# SCH_circular-led_2022-01-28.net
KiCad netlist of a schematic drawn in EasyEDA
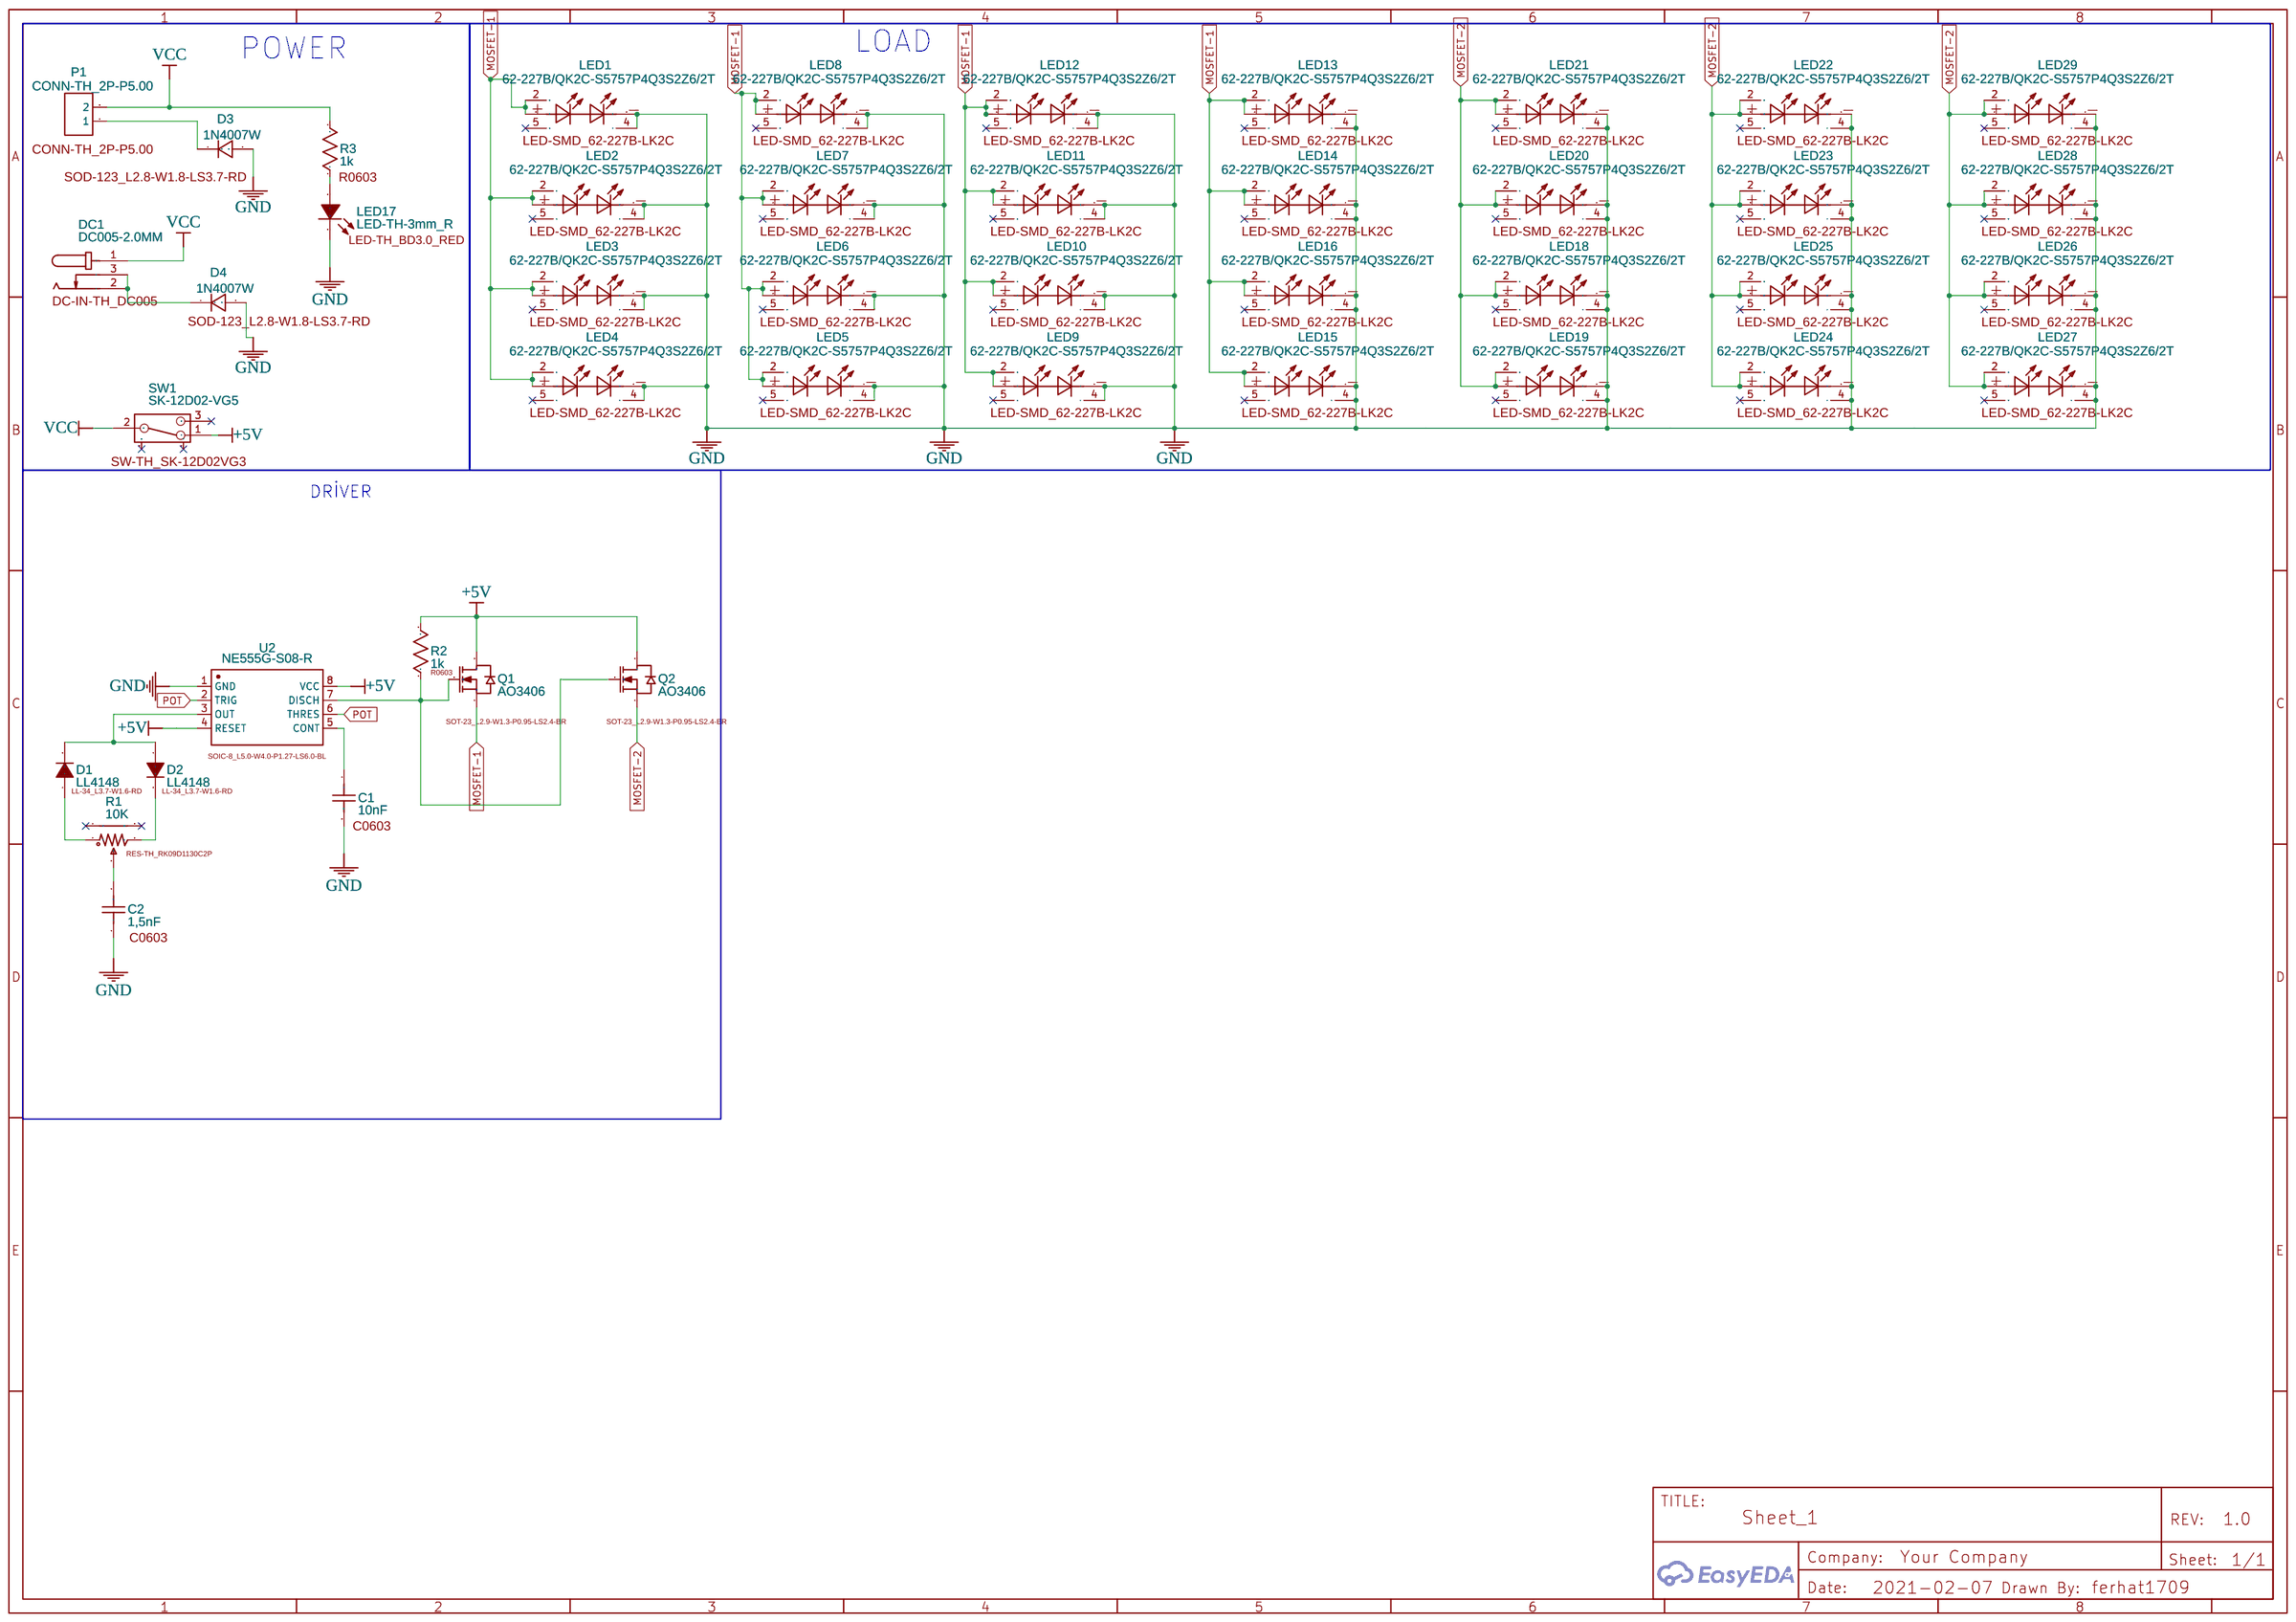
[diagram p0: schematic sheet]

(export (version "E")
  (design (tool "Eeschema 10.0.6"))
  (components
    (comp (ref "C1") (value "10nF") (libsource (lib "") (part "C_0603_US")))
    (comp (ref "C2") (value "1,5nF") (libsource (lib "") (part "C_0603_US_1")))
    (comp (ref "D1")
      (value "LL4148")
      (fields (field (name "BOM_Supplier Part") "C9808"))
      (libsource (lib "") (part "LL4148"))
    )
    (comp (ref "D2")
      (value "LL4148")
      (fields (field (name "BOM_Supplier Part") "C9808"))
      (libsource (lib "") (part "LL4148_1"))
    )
    (comp (ref "D3")
      (value "1N4007W")
      (fields (field (name "BOM_Supplier Part") "C328592"))
      (libsource (lib "") (part "1N4007W"))
    )
    (comp (ref "D4")
      (value "1N4007W")
      (fields (field (name "BOM_Supplier Part") "C328592"))
      (libsource (lib "") (part "1N4007W_1"))
    )
    (comp (ref "DC1")
      (value "DC005-2.0MM")
      (fields (field (name "BOM_Supplier Part") "C111567"))
      (libsource (lib "") (part "DC005-2.0MM"))
    )
    (comp (ref "LED1")
      (value "62-227B/QK2C-S5757P4Q3S2Z6/2T")
      (fields (field (name "BOM_Supplier Part") "C282160"))
      (libsource (lib "") (part "62-227B/QK2C-S5757P4Q3S2Z6/2T"))
    )
    (comp (ref "LED2")
      (value "62-227B/QK2C-S5757P4Q3S2Z6/2T")
      (fields (field (name "BOM_Supplier Part") "C282160"))
      (libsource (lib "") (part "62-227B/QK2C-S5757P4Q3S2Z6/2T"))
    )
    (comp (ref "LED3")
      (value "62-227B/QK2C-S5757P4Q3S2Z6/2T")
      (fields (field (name "BOM_Supplier Part") "C282160"))
      (libsource (lib "") (part "62-227B/QK2C-S5757P4Q3S2Z6/2T"))
    )
    (comp (ref "LED4")
      (value "62-227B/QK2C-S5757P4Q3S2Z6/2T")
      (fields (field (name "BOM_Supplier Part") "C282160"))
      (libsource (lib "") (part "62-227B/QK2C-S5757P4Q3S2Z6/2T"))
    )
    (comp (ref "LED5")
      (value "62-227B/QK2C-S5757P4Q3S2Z6/2T")
      (fields (field (name "BOM_Supplier Part") "C282160"))
      (libsource (lib "") (part "62-227B/QK2C-S5757P4Q3S2Z6/2T"))
    )
    (comp (ref "LED6")
      (value "62-227B/QK2C-S5757P4Q3S2Z6/2T")
      (fields (field (name "BOM_Supplier Part") "C282160"))
      (libsource (lib "") (part "62-227B/QK2C-S5757P4Q3S2Z6/2T"))
    )
    (comp (ref "LED7")
      (value "62-227B/QK2C-S5757P4Q3S2Z6/2T")
      (fields (field (name "BOM_Supplier Part") "C282160"))
      (libsource (lib "") (part "62-227B/QK2C-S5757P4Q3S2Z6/2T"))
    )
    (comp (ref "LED8")
      (value "62-227B/QK2C-S5757P4Q3S2Z6/2T")
      (fields (field (name "BOM_Supplier Part") "C282160"))
      (libsource (lib "") (part "62-227B/QK2C-S5757P4Q3S2Z6/2T"))
    )
    (comp (ref "LED9")
      (value "62-227B/QK2C-S5757P4Q3S2Z6/2T")
      (fields (field (name "BOM_Supplier Part") "C282160"))
      (libsource (lib "") (part "62-227B/QK2C-S5757P4Q3S2Z6/2T"))
    )
    (comp (ref "LED10")
      (value "62-227B/QK2C-S5757P4Q3S2Z6/2T")
      (fields (field (name "BOM_Supplier Part") "C282160"))
      (libsource (lib "") (part "62-227B/QK2C-S5757P4Q3S2Z6/2T"))
    )
    (comp (ref "LED11")
      (value "62-227B/QK2C-S5757P4Q3S2Z6/2T")
      (fields (field (name "BOM_Supplier Part") "C282160"))
      (libsource (lib "") (part "62-227B/QK2C-S5757P4Q3S2Z6/2T"))
    )
    (comp (ref "LED12")
      (value "62-227B/QK2C-S5757P4Q3S2Z6/2T")
      (fields (field (name "BOM_Supplier Part") "C282160"))
      (libsource (lib "") (part "62-227B/QK2C-S5757P4Q3S2Z6/2T"))
    )
    (comp (ref "LED13")
      (value "62-227B/QK2C-S5757P4Q3S2Z6/2T")
      (fields (field (name "BOM_Supplier Part") "C282160"))
      (libsource (lib "") (part "62-227B/QK2C-S5757P4Q3S2Z6/2T"))
    )
    (comp (ref "LED14")
      (value "62-227B/QK2C-S5757P4Q3S2Z6/2T")
      (fields (field (name "BOM_Supplier Part") "C282160"))
      (libsource (lib "") (part "62-227B/QK2C-S5757P4Q3S2Z6/2T"))
    )
    (comp (ref "LED15")
      (value "62-227B/QK2C-S5757P4Q3S2Z6/2T")
      (fields (field (name "BOM_Supplier Part") "C282160"))
      (libsource (lib "") (part "62-227B/QK2C-S5757P4Q3S2Z6/2T"))
    )
    (comp (ref "LED16")
      (value "62-227B/QK2C-S5757P4Q3S2Z6/2T")
      (fields (field (name "BOM_Supplier Part") "C282160"))
      (libsource (lib "") (part "62-227B/QK2C-S5757P4Q3S2Z6/2T"))
    )
    (comp (ref "LED17")
      (value "LED-TH-3mm_R")
      (fields
        (field (name "BOM_Manufacturer Part") "204-10SDRD/S530-A3-L")
        (field (name "BOM_Supplier Part") "C84774")
      )
      (libsource (lib "") (part "LED-TH-3mm_R"))
    )
    (comp (ref "LED18")
      (value "62-227B/QK2C-S5757P4Q3S2Z6/2T")
      (fields (field (name "BOM_Supplier Part") "C282160"))
      (libsource (lib "") (part "62-227B/QK2C-S5757P4Q3S2Z6/2T"))
    )
    (comp (ref "LED19")
      (value "62-227B/QK2C-S5757P4Q3S2Z6/2T")
      (fields (field (name "BOM_Supplier Part") "C282160"))
      (libsource (lib "") (part "62-227B/QK2C-S5757P4Q3S2Z6/2T"))
    )
    (comp (ref "LED20")
      (value "62-227B/QK2C-S5757P4Q3S2Z6/2T")
      (fields (field (name "BOM_Supplier Part") "C282160"))
      (libsource (lib "") (part "62-227B/QK2C-S5757P4Q3S2Z6/2T"))
    )
    (comp (ref "LED21")
      (value "62-227B/QK2C-S5757P4Q3S2Z6/2T")
      (fields (field (name "BOM_Supplier Part") "C282160"))
      (libsource (lib "") (part "62-227B/QK2C-S5757P4Q3S2Z6/2T"))
    )
    (comp (ref "LED22")
      (value "62-227B/QK2C-S5757P4Q3S2Z6/2T")
      (fields (field (name "BOM_Supplier Part") "C282160"))
      (libsource (lib "") (part "62-227B/QK2C-S5757P4Q3S2Z6/2T"))
    )
    (comp (ref "LED23")
      (value "62-227B/QK2C-S5757P4Q3S2Z6/2T")
      (fields (field (name "BOM_Supplier Part") "C282160"))
      (libsource (lib "") (part "62-227B/QK2C-S5757P4Q3S2Z6/2T"))
    )
    (comp (ref "LED24")
      (value "62-227B/QK2C-S5757P4Q3S2Z6/2T")
      (fields (field (name "BOM_Supplier Part") "C282160"))
      (libsource (lib "") (part "62-227B/QK2C-S5757P4Q3S2Z6/2T"))
    )
    (comp (ref "LED25")
      (value "62-227B/QK2C-S5757P4Q3S2Z6/2T")
      (fields (field (name "BOM_Supplier Part") "C282160"))
      (libsource (lib "") (part "62-227B/QK2C-S5757P4Q3S2Z6/2T"))
    )
    (comp (ref "LED26")
      (value "62-227B/QK2C-S5757P4Q3S2Z6/2T")
      (fields (field (name "BOM_Supplier Part") "C282160"))
      (libsource (lib "") (part "62-227B/QK2C-S5757P4Q3S2Z6/2T"))
    )
    (comp (ref "LED27")
      (value "62-227B/QK2C-S5757P4Q3S2Z6/2T")
      (fields (field (name "BOM_Supplier Part") "C282160"))
      (libsource (lib "") (part "62-227B/QK2C-S5757P4Q3S2Z6/2T"))
    )
    (comp (ref "LED28")
      (value "62-227B/QK2C-S5757P4Q3S2Z6/2T")
      (fields (field (name "BOM_Supplier Part") "C282160"))
      (libsource (lib "") (part "62-227B/QK2C-S5757P4Q3S2Z6/2T"))
    )
    (comp (ref "LED29")
      (value "62-227B/QK2C-S5757P4Q3S2Z6/2T")
      (fields (field (name "BOM_Supplier Part") "C282160"))
      (libsource (lib "") (part "62-227B/QK2C-S5757P4Q3S2Z6/2T"))
    )
    (comp (ref "P1") (value "CONN-TH_2P-P5.00") (libsource (lib "") (part "CONN-TH_2P-P5.00")))
    (comp (ref "Q1")
      (value "AO3406")
      (fields (field (name "BOM_Supplier Part") "C88051"))
      (libsource (lib "") (part "AO3406"))
    )
    (comp (ref "Q2")
      (value "AO3406")
      (fields (field (name "BOM_Supplier Part") "C88051"))
      (libsource (lib "") (part "AO3406"))
    )
    (comp (ref "R1")
      (value "10K")
      (fields
        (field (name "BOM_Manufacturer Part") "RK09D1130C2P")
        (field (name "BOM_Supplier Part") "C361173")
      )
      (libsource (lib "") (part "RK09D1130C2P"))
    )
    (comp (ref "R2") (value "1k") (libsource (lib "") (part "R_0603_US")))
    (comp (ref "R3") (value "1k") (libsource (lib "") (part "R_0603_US_1")))
    (comp (ref "SW1")
      (value "SK-12D02-VG5")
      (fields (field (name "BOM_Supplier Part") "C136722"))
      (libsource (lib "") (part "SK-12D02-VG5"))
    )
    (comp (ref "U2")
      (value "NE555G-S08-R")
      (fields (field (name "BOM_Supplier Part") "C75529"))
      (libsource (lib "") (part "NE555G-S08-R"))
    )
  )
  (nets
    (net (code "1") (name "+5V") (class "Default")
      (node (ref "Q1") (pin "3") (pinfunction "D_3") (pintype "unspecified"))
      (node (ref "Q2") (pin "3") (pinfunction "D_3") (pintype "unspecified"))
      (node (ref "R2") (pin "2") (pinfunction "2_2") (pintype "unspecified"))
      (node (ref "SW1") (pin "1") (pinfunction "1_1") (pintype "unspecified"))
      (node (ref "U2") (pin "4") (pinfunction "RESET_4") (pintype "unspecified"))
      (node (ref "U2") (pin "8") (pinfunction "VCC_8") (pintype "unspecified"))
    )
    (net (code "2") (name "GND") (class "Default")
      (node (ref "C1") (pin "2") (pinfunction "2_2") (pintype "unspecified"))
      (node (ref "C2") (pin "1") (pinfunction "1_1") (pintype "unspecified"))
      (node (ref "D3") (pin "2") (pinfunction "2_2") (pintype "unspecified"))
      (node (ref "D4") (pin "2") (pinfunction "2_2") (pintype "unspecified"))
      (node (ref "LED1") (pin "1") (pinfunction "1_1") (pintype "unspecified"))
      (node (ref "LED1") (pin "4") (pinfunction "4_4") (pintype "unspecified"))
      (node (ref "LED10") (pin "1") (pinfunction "1_1") (pintype "unspecified"))
      (node (ref "LED10") (pin "4") (pinfunction "4_4") (pintype "unspecified"))
      (node (ref "LED11") (pin "1") (pinfunction "1_1") (pintype "unspecified"))
      (node (ref "LED11") (pin "4") (pinfunction "4_4") (pintype "unspecified"))
      (node (ref "LED12") (pin "1") (pinfunction "1_1") (pintype "unspecified"))
      (node (ref "LED12") (pin "4") (pinfunction "4_4") (pintype "unspecified"))
      (node (ref "LED13") (pin "1") (pinfunction "1_1") (pintype "unspecified"))
      (node (ref "LED13") (pin "4") (pinfunction "4_4") (pintype "unspecified"))
      (node (ref "LED14") (pin "1") (pinfunction "1_1") (pintype "unspecified"))
      (node (ref "LED14") (pin "4") (pinfunction "4_4") (pintype "unspecified"))
      (node (ref "LED15") (pin "1") (pinfunction "1_1") (pintype "unspecified"))
      (node (ref "LED15") (pin "4") (pinfunction "4_4") (pintype "unspecified"))
      (node (ref "LED16") (pin "1") (pinfunction "1_1") (pintype "unspecified"))
      (node (ref "LED16") (pin "4") (pinfunction "4_4") (pintype "unspecified"))
      (node (ref "LED17") (pin "2") (pinfunction "2_2") (pintype "unspecified"))
      (node (ref "LED18") (pin "1") (pinfunction "1_1") (pintype "unspecified"))
      (node (ref "LED18") (pin "4") (pinfunction "4_4") (pintype "unspecified"))
      (node (ref "LED19") (pin "1") (pinfunction "1_1") (pintype "unspecified"))
      (node (ref "LED19") (pin "4") (pinfunction "4_4") (pintype "unspecified"))
      (node (ref "LED2") (pin "1") (pinfunction "1_1") (pintype "unspecified"))
      (node (ref "LED2") (pin "4") (pinfunction "4_4") (pintype "unspecified"))
      (node (ref "LED20") (pin "1") (pinfunction "1_1") (pintype "unspecified"))
      (node (ref "LED20") (pin "4") (pinfunction "4_4") (pintype "unspecified"))
      (node (ref "LED21") (pin "1") (pinfunction "1_1") (pintype "unspecified"))
      (node (ref "LED21") (pin "4") (pinfunction "4_4") (pintype "unspecified"))
      (node (ref "LED22") (pin "1") (pinfunction "1_1") (pintype "unspecified"))
      (node (ref "LED22") (pin "4") (pinfunction "4_4") (pintype "unspecified"))
      (node (ref "LED23") (pin "1") (pinfunction "1_1") (pintype "unspecified"))
      (node (ref "LED23") (pin "4") (pinfunction "4_4") (pintype "unspecified"))
      (node (ref "LED24") (pin "1") (pinfunction "1_1") (pintype "unspecified"))
      (node (ref "LED24") (pin "4") (pinfunction "4_4") (pintype "unspecified"))
      (node (ref "LED25") (pin "1") (pinfunction "1_1") (pintype "unspecified"))
      (node (ref "LED25") (pin "4") (pinfunction "4_4") (pintype "unspecified"))
      (node (ref "LED26") (pin "1") (pinfunction "1_1") (pintype "unspecified"))
      (node (ref "LED26") (pin "4") (pinfunction "4_4") (pintype "unspecified"))
      (node (ref "LED27") (pin "1") (pinfunction "1_1") (pintype "unspecified"))
      (node (ref "LED27") (pin "4") (pinfunction "4_4") (pintype "unspecified"))
      (node (ref "LED28") (pin "1") (pinfunction "1_1") (pintype "unspecified"))
      (node (ref "LED28") (pin "4") (pinfunction "4_4") (pintype "unspecified"))
      (node (ref "LED29") (pin "1") (pinfunction "1_1") (pintype "unspecified"))
      (node (ref "LED29") (pin "4") (pinfunction "4_4") (pintype "unspecified"))
      (node (ref "LED3") (pin "1") (pinfunction "1_1") (pintype "unspecified"))
      (node (ref "LED3") (pin "4") (pinfunction "4_4") (pintype "unspecified"))
      (node (ref "LED4") (pin "1") (pinfunction "1_1") (pintype "unspecified"))
      (node (ref "LED4") (pin "4") (pinfunction "4_4") (pintype "unspecified"))
      (node (ref "LED5") (pin "1") (pinfunction "1_1") (pintype "unspecified"))
      (node (ref "LED5") (pin "4") (pinfunction "4_4") (pintype "unspecified"))
      (node (ref "LED6") (pin "1") (pinfunction "1_1") (pintype "unspecified"))
      (node (ref "LED6") (pin "4") (pinfunction "4_4") (pintype "unspecified"))
      (node (ref "LED7") (pin "1") (pinfunction "1_1") (pintype "unspecified"))
      (node (ref "LED7") (pin "4") (pinfunction "4_4") (pintype "unspecified"))
      (node (ref "LED8") (pin "1") (pinfunction "1_1") (pintype "unspecified"))
      (node (ref "LED8") (pin "4") (pinfunction "4_4") (pintype "unspecified"))
      (node (ref "LED9") (pin "1") (pinfunction "1_1") (pintype "unspecified"))
      (node (ref "LED9") (pin "4") (pinfunction "4_4") (pintype "unspecified"))
      (node (ref "U2") (pin "1") (pinfunction "GND_1") (pintype "unspecified"))
    )
    (net (code "3") (name "MOSFET-1") (class "Default")
      (node (ref "LED1") (pin "2") (pinfunction "2_2") (pintype "unspecified"))
      (node (ref "LED1") (pin "3") (pinfunction "3_3") (pintype "unspecified"))
      (node (ref "LED10") (pin "2") (pinfunction "2_2") (pintype "unspecified"))
      (node (ref "LED10") (pin "3") (pinfunction "3_3") (pintype "unspecified"))
      (node (ref "LED11") (pin "2") (pinfunction "2_2") (pintype "unspecified"))
      (node (ref "LED11") (pin "3") (pinfunction "3_3") (pintype "unspecified"))
      (node (ref "LED12") (pin "2") (pinfunction "2_2") (pintype "unspecified"))
      (node (ref "LED12") (pin "3") (pinfunction "3_3") (pintype "unspecified"))
      (node (ref "LED13") (pin "2") (pinfunction "2_2") (pintype "unspecified"))
      (node (ref "LED13") (pin "3") (pinfunction "3_3") (pintype "unspecified"))
      (node (ref "LED14") (pin "2") (pinfunction "2_2") (pintype "unspecified"))
      (node (ref "LED14") (pin "3") (pinfunction "3_3") (pintype "unspecified"))
      (node (ref "LED15") (pin "2") (pinfunction "2_2") (pintype "unspecified"))
      (node (ref "LED15") (pin "3") (pinfunction "3_3") (pintype "unspecified"))
      (node (ref "LED16") (pin "2") (pinfunction "2_2") (pintype "unspecified"))
      (node (ref "LED16") (pin "3") (pinfunction "3_3") (pintype "unspecified"))
      (node (ref "LED2") (pin "2") (pinfunction "2_2") (pintype "unspecified"))
      (node (ref "LED2") (pin "3") (pinfunction "3_3") (pintype "unspecified"))
      (node (ref "LED3") (pin "2") (pinfunction "2_2") (pintype "unspecified"))
      (node (ref "LED3") (pin "3") (pinfunction "3_3") (pintype "unspecified"))
      (node (ref "LED4") (pin "2") (pinfunction "2_2") (pintype "unspecified"))
      (node (ref "LED4") (pin "3") (pinfunction "3_3") (pintype "unspecified"))
      (node (ref "LED5") (pin "2") (pinfunction "2_2") (pintype "unspecified"))
      (node (ref "LED5") (pin "3") (pinfunction "3_3") (pintype "unspecified"))
      (node (ref "LED6") (pin "2") (pinfunction "2_2") (pintype "unspecified"))
      (node (ref "LED6") (pin "3") (pinfunction "3_3") (pintype "unspecified"))
      (node (ref "LED7") (pin "2") (pinfunction "2_2") (pintype "unspecified"))
      (node (ref "LED7") (pin "3") (pinfunction "3_3") (pintype "unspecified"))
      (node (ref "LED8") (pin "2") (pinfunction "2_2") (pintype "unspecified"))
      (node (ref "LED8") (pin "3") (pinfunction "3_3") (pintype "unspecified"))
      (node (ref "LED9") (pin "2") (pinfunction "2_2") (pintype "unspecified"))
      (node (ref "LED9") (pin "3") (pinfunction "3_3") (pintype "unspecified"))
      (node (ref "Q1") (pin "2") (pinfunction "S_2") (pintype "unspecified"))
    )
    (net (code "4") (name "MOSFET-2") (class "Default")
      (node (ref "LED18") (pin "2") (pinfunction "2_2") (pintype "unspecified"))
      (node (ref "LED18") (pin "3") (pinfunction "3_3") (pintype "unspecified"))
      (node (ref "LED19") (pin "2") (pinfunction "2_2") (pintype "unspecified"))
      (node (ref "LED19") (pin "3") (pinfunction "3_3") (pintype "unspecified"))
      (node (ref "LED20") (pin "2") (pinfunction "2_2") (pintype "unspecified"))
      (node (ref "LED20") (pin "3") (pinfunction "3_3") (pintype "unspecified"))
      (node (ref "LED21") (pin "2") (pinfunction "2_2") (pintype "unspecified"))
      (node (ref "LED21") (pin "3") (pinfunction "3_3") (pintype "unspecified"))
      (node (ref "LED22") (pin "2") (pinfunction "2_2") (pintype "unspecified"))
      (node (ref "LED22") (pin "3") (pinfunction "3_3") (pintype "unspecified"))
      (node (ref "LED23") (pin "2") (pinfunction "2_2") (pintype "unspecified"))
      (node (ref "LED23") (pin "3") (pinfunction "3_3") (pintype "unspecified"))
      (node (ref "LED24") (pin "2") (pinfunction "2_2") (pintype "unspecified"))
      (node (ref "LED24") (pin "3") (pinfunction "3_3") (pintype "unspecified"))
      (node (ref "LED25") (pin "2") (pinfunction "2_2") (pintype "unspecified"))
      (node (ref "LED25") (pin "3") (pinfunction "3_3") (pintype "unspecified"))
      (node (ref "LED26") (pin "2") (pinfunction "2_2") (pintype "unspecified"))
      (node (ref "LED26") (pin "3") (pinfunction "3_3") (pintype "unspecified"))
      (node (ref "LED27") (pin "2") (pinfunction "2_2") (pintype "unspecified"))
      (node (ref "LED27") (pin "3") (pinfunction "3_3") (pintype "unspecified"))
      (node (ref "LED28") (pin "2") (pinfunction "2_2") (pintype "unspecified"))
      (node (ref "LED28") (pin "3") (pinfunction "3_3") (pintype "unspecified"))
      (node (ref "LED29") (pin "2") (pinfunction "2_2") (pintype "unspecified"))
      (node (ref "LED29") (pin "3") (pinfunction "3_3") (pintype "unspecified"))
      (node (ref "Q2") (pin "2") (pinfunction "S_2") (pintype "unspecified"))
    )
    (net (code "5") (name "Net-(C2-Pad2)") (class "Default")
      (node (ref "C2") (pin "2") (pinfunction "2_2") (pintype "unspecified"))
      (node (ref "R1") (pin "2") (pinfunction "2_2") (pintype "unspecified"))
    )
    (net (code "6") (name "Net-(D1-A)") (class "Default")
      (node (ref "D1") (pin "1") (pinfunction "A_1") (pintype "unspecified"))
      (node (ref "R1") (pin "1") (pinfunction "1_1") (pintype "unspecified"))
    )
    (net (code "7") (name "Net-(D1-K)") (class "Default")
      (node (ref "D1") (pin "2") (pinfunction "K_2") (pintype "unspecified"))
      (node (ref "D2") (pin "1") (pinfunction "A_1") (pintype "unspecified"))
      (node (ref "U2") (pin "3") (pinfunction "OUT_3") (pintype "unspecified"))
    )
    (net (code "8") (name "Net-(D2-K)") (class "Default")
      (node (ref "D2") (pin "2") (pinfunction "K_2") (pintype "unspecified"))
      (node (ref "R1") (pin "3") (pinfunction "3_3") (pintype "unspecified"))
    )
    (net (code "9") (name "Net-(D3-Pad1)") (class "Default")
      (node (ref "D3") (pin "1") (pinfunction "1_1") (pintype "unspecified"))
      (node (ref "P1") (pin "1") (pinfunction "1_1") (pintype "unspecified"))
    )
    (net (code "10") (name "Net-(D4-Pad1)") (class "Default")
      (node (ref "D4") (pin "1") (pinfunction "1_1") (pintype "unspecified"))
      (node (ref "DC1") (pin "2") (pinfunction "2_2") (pintype "unspecified"))
      (node (ref "DC1") (pin "3") (pinfunction "3_3") (pintype "unspecified"))
    )
    (net (code "11") (name "Net-(LED17-Pad1)") (class "Default")
      (node (ref "LED17") (pin "1") (pinfunction "1_1") (pintype "unspecified"))
      (node (ref "R3") (pin "1") (pinfunction "1_1") (pintype "unspecified"))
    )
    (net (code "12") (name "Net-(Q1-G)") (class "Default")
      (node (ref "Q1") (pin "1") (pinfunction "G_1") (pintype "unspecified"))
      (node (ref "Q2") (pin "1") (pinfunction "G_1") (pintype "unspecified"))
      (node (ref "R2") (pin "1") (pinfunction "1_1") (pintype "unspecified"))
      (node (ref "U2") (pin "7") (pinfunction "DISCH_7") (pintype "unspecified"))
    )
    (net (code "13") (name "Net-(U2-CONT)") (class "Default")
      (node (ref "C1") (pin "1") (pinfunction "1_1") (pintype "unspecified"))
      (node (ref "U2") (pin "5") (pinfunction "CONT_5") (pintype "unspecified"))
    )
    (net (code "14") (name "POT") (class "Default")
      (node (ref "U2") (pin "2") (pinfunction "TRIG_2") (pintype "unspecified"))
      (node (ref "U2") (pin "6") (pinfunction "THRES_6") (pintype "unspecified"))
    )
    (net (code "15") (name "VCC") (class "Default")
      (node (ref "DC1") (pin "1") (pinfunction "1_1") (pintype "unspecified"))
      (node (ref "P1") (pin "2") (pinfunction "2_2") (pintype "unspecified"))
      (node (ref "R3") (pin "2") (pinfunction "2_2") (pintype "unspecified"))
      (node (ref "SW1") (pin "2") (pinfunction "2_2") (pintype "unspecified"))
    )
    (net (code "16") (name "unconnected-(LED1-Pad5)") (class "Default")
      (node (ref "LED1") (pin "5") (pinfunction "5_5") (pintype "unspecified+no_connect"))
    )
    (net (code "17") (name "unconnected-(LED2-Pad5)") (class "Default")
      (node (ref "LED2") (pin "5") (pinfunction "5_5") (pintype "unspecified+no_connect"))
    )
    (net (code "18") (name "unconnected-(LED3-Pad5)") (class "Default")
      (node (ref "LED3") (pin "5") (pinfunction "5_5") (pintype "unspecified+no_connect"))
    )
    (net (code "19") (name "unconnected-(LED4-Pad5)") (class "Default")
      (node (ref "LED4") (pin "5") (pinfunction "5_5") (pintype "unspecified+no_connect"))
    )
    (net (code "20") (name "unconnected-(LED5-Pad5)") (class "Default")
      (node (ref "LED5") (pin "5") (pinfunction "5_5") (pintype "unspecified+no_connect"))
    )
    (net (code "21") (name "unconnected-(LED6-Pad5)") (class "Default")
      (node (ref "LED6") (pin "5") (pinfunction "5_5") (pintype "unspecified+no_connect"))
    )
    (net (code "22") (name "unconnected-(LED7-Pad5)") (class "Default")
      (node (ref "LED7") (pin "5") (pinfunction "5_5") (pintype "unspecified+no_connect"))
    )
    (net (code "23") (name "unconnected-(LED8-Pad5)") (class "Default")
      (node (ref "LED8") (pin "5") (pinfunction "5_5") (pintype "unspecified+no_connect"))
    )
    (net (code "24") (name "unconnected-(LED9-Pad5)") (class "Default")
      (node (ref "LED9") (pin "5") (pinfunction "5_5") (pintype "unspecified+no_connect"))
    )
    (net (code "25") (name "unconnected-(LED10-Pad5)") (class "Default")
      (node (ref "LED10") (pin "5") (pinfunction "5_5") (pintype "unspecified+no_connect"))
    )
    (net (code "26") (name "unconnected-(LED11-Pad5)") (class "Default")
      (node (ref "LED11") (pin "5") (pinfunction "5_5") (pintype "unspecified+no_connect"))
    )
    (net (code "27") (name "unconnected-(LED12-Pad5)") (class "Default")
      (node (ref "LED12") (pin "5") (pinfunction "5_5") (pintype "unspecified+no_connect"))
    )
    (net (code "28") (name "unconnected-(LED13-Pad5)") (class "Default")
      (node (ref "LED13") (pin "5") (pinfunction "5_5") (pintype "unspecified+no_connect"))
    )
    (net (code "29") (name "unconnected-(LED14-Pad5)") (class "Default")
      (node (ref "LED14") (pin "5") (pinfunction "5_5") (pintype "unspecified+no_connect"))
    )
    (net (code "30") (name "unconnected-(LED15-Pad5)") (class "Default")
      (node (ref "LED15") (pin "5") (pinfunction "5_5") (pintype "unspecified+no_connect"))
    )
    (net (code "31") (name "unconnected-(LED16-Pad5)") (class "Default")
      (node (ref "LED16") (pin "5") (pinfunction "5_5") (pintype "unspecified+no_connect"))
    )
    (net (code "32") (name "unconnected-(LED18-Pad5)") (class "Default")
      (node (ref "LED18") (pin "5") (pinfunction "5_5") (pintype "unspecified+no_connect"))
    )
    (net (code "33") (name "unconnected-(LED19-Pad5)") (class "Default")
      (node (ref "LED19") (pin "5") (pinfunction "5_5") (pintype "unspecified+no_connect"))
    )
    (net (code "34") (name "unconnected-(LED20-Pad5)") (class "Default")
      (node (ref "LED20") (pin "5") (pinfunction "5_5") (pintype "unspecified+no_connect"))
    )
    (net (code "35") (name "unconnected-(LED21-Pad5)") (class "Default")
      (node (ref "LED21") (pin "5") (pinfunction "5_5") (pintype "unspecified+no_connect"))
    )
    (net (code "36") (name "unconnected-(LED22-Pad5)") (class "Default")
      (node (ref "LED22") (pin "5") (pinfunction "5_5") (pintype "unspecified+no_connect"))
    )
    (net (code "37") (name "unconnected-(LED23-Pad5)") (class "Default")
      (node (ref "LED23") (pin "5") (pinfunction "5_5") (pintype "unspecified+no_connect"))
    )
    (net (code "38") (name "unconnected-(LED24-Pad5)") (class "Default")
      (node (ref "LED24") (pin "5") (pinfunction "5_5") (pintype "unspecified+no_connect"))
    )
    (net (code "39") (name "unconnected-(LED25-Pad5)") (class "Default")
      (node (ref "LED25") (pin "5") (pinfunction "5_5") (pintype "unspecified+no_connect"))
    )
    (net (code "40") (name "unconnected-(LED26-Pad5)") (class "Default")
      (node (ref "LED26") (pin "5") (pinfunction "5_5") (pintype "unspecified+no_connect"))
    )
    (net (code "41") (name "unconnected-(LED27-Pad5)") (class "Default")
      (node (ref "LED27") (pin "5") (pinfunction "5_5") (pintype "unspecified+no_connect"))
    )
    (net (code "42") (name "unconnected-(LED28-Pad5)") (class "Default")
      (node (ref "LED28") (pin "5") (pinfunction "5_5") (pintype "unspecified+no_connect"))
    )
    (net (code "43") (name "unconnected-(LED29-Pad5)") (class "Default")
      (node (ref "LED29") (pin "5") (pinfunction "5_5") (pintype "unspecified+no_connect"))
    )
    (net (code "44") (name "unconnected-(R1-Pad4)") (class "Default")
      (node (ref "R1") (pin "4") (pinfunction "4_4") (pintype "unspecified+no_connect"))
    )
    (net (code "45") (name "unconnected-(R1-Pad5)") (class "Default")
      (node (ref "R1") (pin "5") (pinfunction "5_5") (pintype "unspecified+no_connect"))
    )
    (net (code "46") (name "unconnected-(SW1-Pad3)") (class "Default")
      (node (ref "SW1") (pin "3") (pinfunction "3_3") (pintype "unspecified+no_connect"))
    )
    (net (code "47") (name "unconnected-(SW1-Pad4)") (class "Default")
      (node (ref "SW1") (pin "4") (pinfunction "4_4") (pintype "unspecified+no_connect"))
    )
    (net (code "48") (name "unconnected-(SW1-Pad5)") (class "Default")
      (node (ref "SW1") (pin "5") (pinfunction "5_5") (pintype "unspecified+no_connect"))
    )
  )
)
